# TRHPSVG_Controls_v2.net
KiCad netlist of a schematic drawn in EAGLE
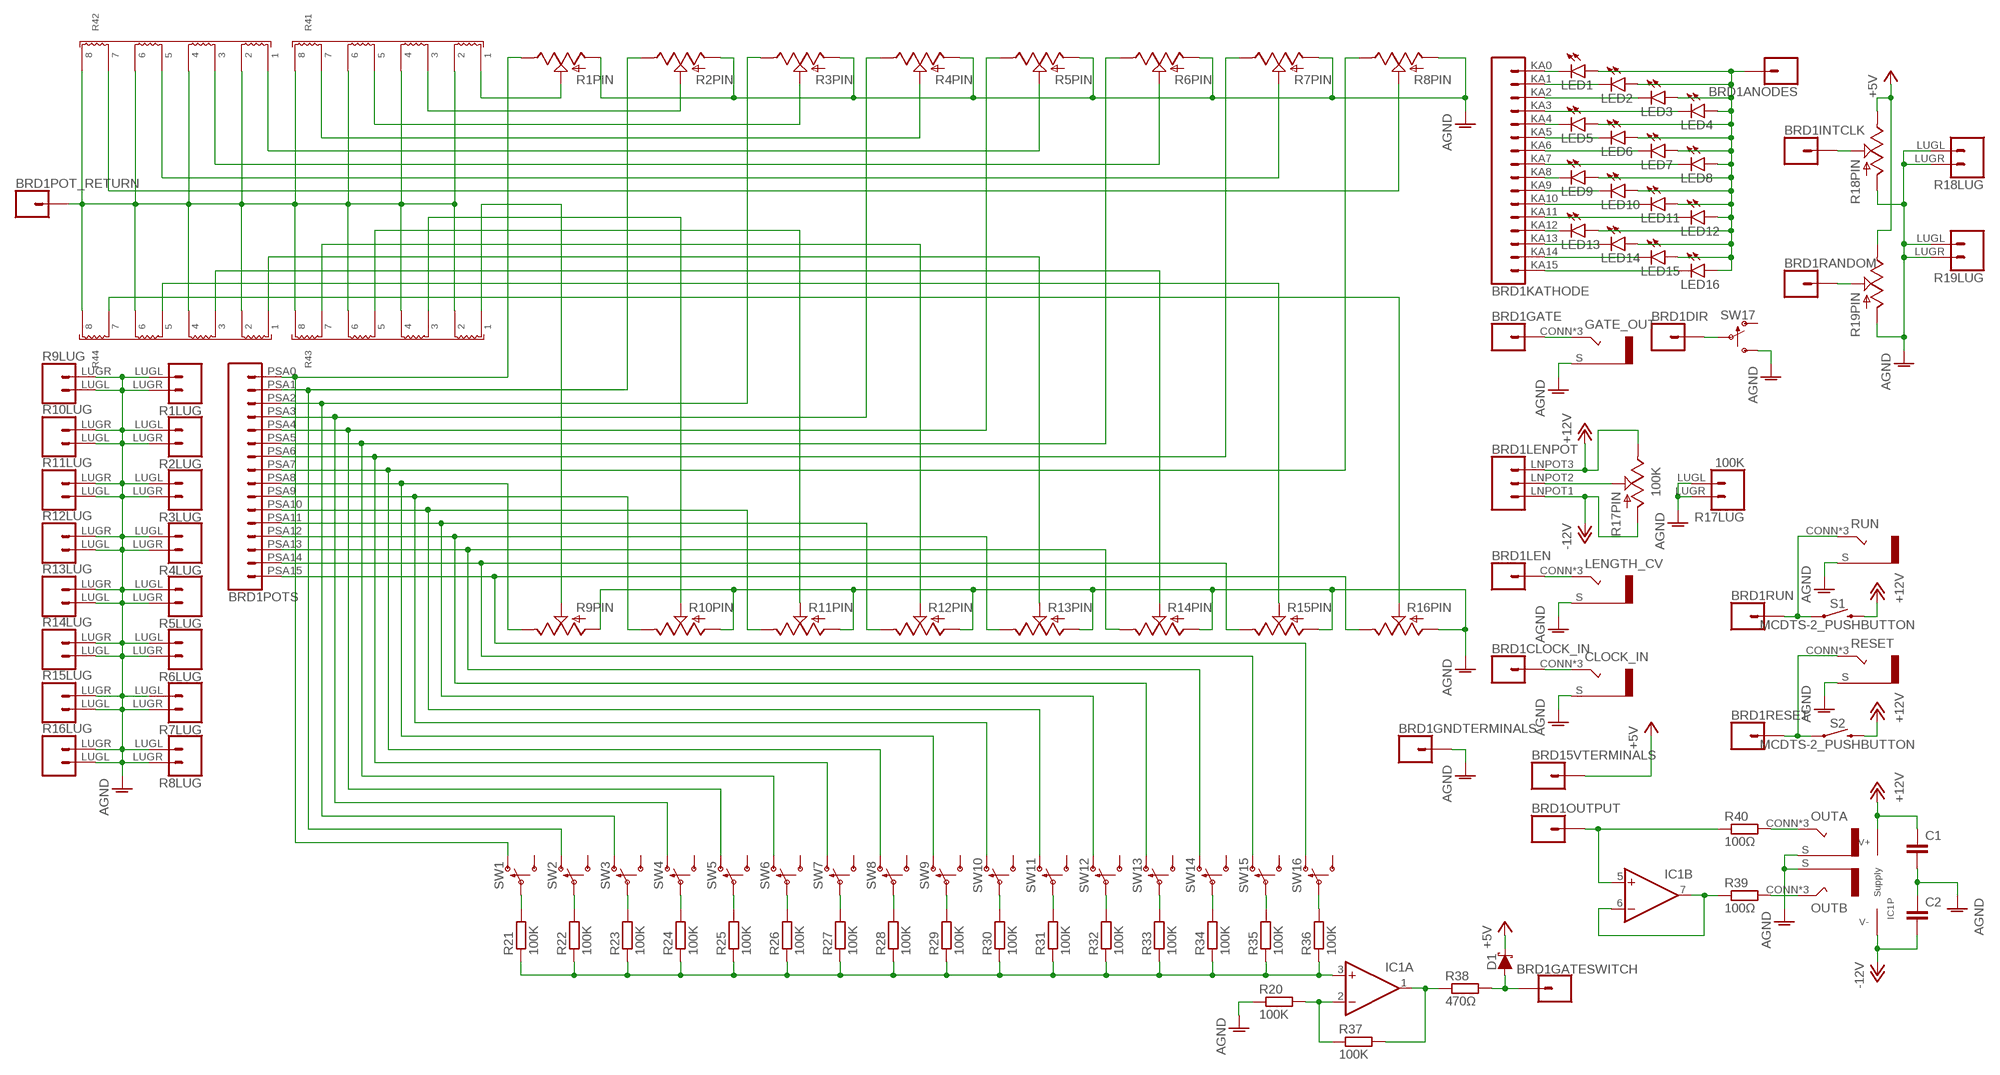
[diagram p0: schematic, sheet 1]

(export (version "E")
  (design (tool "Eeschema 10.0.6"))
  (components
    (comp (ref "BRD1")
      (value "TRHPSVG_LINK")
      (footprint "eagle-import:TRHPSVG")
      (libsource (lib "eagle-import") (part "TRHPSVG_LINK"))
    )
    (comp (ref "C1")
      (value "C-EU050-025X075")
      (footprint "eagle-import:C050-025X075")
      (libsource (lib "eagle-import") (part "C-EU050-025X075"))
    )
    (comp (ref "C2")
      (value "C-EU050-025X075")
      (footprint "eagle-import:C050-025X075")
      (libsource (lib "eagle-import") (part "C-EU050-025X075"))
    )
    (comp (ref "CLOCK_IN")
      (value "COMBI-JACK")
      (footprint "eagle-import:COMBOJACK_PANEL")
      (libsource (lib "eagle-import") (part "COMBI-JACK"))
    )
    (comp (ref "D1")
      (value "SCHOTTKY_DO35")
      (footprint "eagle-import:DO35-7")
      (libsource (lib "eagle-import") (part "SCHOTTKY_DO35"))
    )
    (comp (ref "GATE_OUT")
      (value "COMBI-JACK")
      (footprint "eagle-import:COMBOJACK_PANEL")
      (libsource (lib "eagle-import") (part "COMBI-JACK"))
    )
    (comp (ref "IC1")
      (value "TL0X2DIL")
      (footprint "eagle-import:DIL08")
      (libsource (lib "eagle-import") (part "TL0X2DIL"))
    )
    (comp (ref "LED1")
      (value "LED3MM")
      (footprint "eagle-import:LED3MM")
      (libsource (lib "eagle-import") (part "LED3MM"))
    )
    (comp (ref "LED2")
      (value "LED3MM")
      (footprint "eagle-import:LED3MM")
      (libsource (lib "eagle-import") (part "LED3MM"))
    )
    (comp (ref "LED3")
      (value "LED3MM")
      (footprint "eagle-import:LED3MM")
      (libsource (lib "eagle-import") (part "LED3MM"))
    )
    (comp (ref "LED4")
      (value "LED3MM")
      (footprint "eagle-import:LED3MM")
      (libsource (lib "eagle-import") (part "LED3MM"))
    )
    (comp (ref "LED5")
      (value "LED3MM")
      (footprint "eagle-import:LED3MM")
      (libsource (lib "eagle-import") (part "LED3MM"))
    )
    (comp (ref "LED6")
      (value "LED3MM")
      (footprint "eagle-import:LED3MM")
      (libsource (lib "eagle-import") (part "LED3MM"))
    )
    (comp (ref "LED7")
      (value "LED3MM")
      (footprint "eagle-import:LED3MM")
      (libsource (lib "eagle-import") (part "LED3MM"))
    )
    (comp (ref "LED8")
      (value "LED3MM")
      (footprint "eagle-import:LED3MM")
      (libsource (lib "eagle-import") (part "LED3MM"))
    )
    (comp (ref "LED9")
      (value "LED3MM")
      (footprint "eagle-import:LED3MM")
      (libsource (lib "eagle-import") (part "LED3MM"))
    )
    (comp (ref "LED10")
      (value "LED3MM")
      (footprint "eagle-import:LED3MM")
      (libsource (lib "eagle-import") (part "LED3MM"))
    )
    (comp (ref "LED11")
      (value "LED3MM")
      (footprint "eagle-import:LED3MM")
      (libsource (lib "eagle-import") (part "LED3MM"))
    )
    (comp (ref "LED12")
      (value "LED3MM")
      (footprint "eagle-import:LED3MM")
      (libsource (lib "eagle-import") (part "LED3MM"))
    )
    (comp (ref "LED13")
      (value "LED3MM")
      (footprint "eagle-import:LED3MM")
      (libsource (lib "eagle-import") (part "LED3MM"))
    )
    (comp (ref "LED14")
      (value "LED3MM")
      (footprint "eagle-import:LED3MM")
      (libsource (lib "eagle-import") (part "LED3MM"))
    )
    (comp (ref "LED15")
      (value "LED3MM")
      (footprint "eagle-import:LED3MM")
      (libsource (lib "eagle-import") (part "LED3MM"))
    )
    (comp (ref "LED16")
      (value "LED3MM")
      (footprint "eagle-import:LED3MM")
      (libsource (lib "eagle-import") (part "LED3MM"))
    )
    (comp (ref "LENGTH_CV")
      (value "COMBI-JACK")
      (footprint "eagle-import:COMBOJACK_PANEL")
      (libsource (lib "eagle-import") (part "COMBI-JACK"))
    )
    (comp (ref "OUTA")
      (value "COMBI-JACK")
      (footprint "eagle-import:COMBOJACK_PANEL")
      (libsource (lib "eagle-import") (part "COMBI-JACK"))
    )
    (comp (ref "OUTB")
      (value "COMBI-JACK")
      (footprint "eagle-import:COMBOJACK_PANEL")
      (libsource (lib "eagle-import") (part "COMBI-JACK"))
    )
    (comp (ref "R1")
      (value "POTENTIOMETER")
      (footprint "eagle-import:ALPHA_RV09_9MMPOT")
      (libsource (lib "eagle-import") (part "POTENTIOMETER"))
    )
    (comp (ref "R2")
      (value "POTENTIOMETER")
      (footprint "eagle-import:ALPHA_RV09_9MMPOT")
      (libsource (lib "eagle-import") (part "POTENTIOMETER"))
    )
    (comp (ref "R3")
      (value "POTENTIOMETER")
      (footprint "eagle-import:ALPHA_RV09_9MMPOT")
      (libsource (lib "eagle-import") (part "POTENTIOMETER"))
    )
    (comp (ref "R4")
      (value "POTENTIOMETER")
      (footprint "eagle-import:ALPHA_RV09_9MMPOT")
      (libsource (lib "eagle-import") (part "POTENTIOMETER"))
    )
    (comp (ref "R5")
      (value "POTENTIOMETER")
      (footprint "eagle-import:ALPHA_RV09_9MMPOT")
      (libsource (lib "eagle-import") (part "POTENTIOMETER"))
    )
    (comp (ref "R6")
      (value "POTENTIOMETER")
      (footprint "eagle-import:ALPHA_RV09_9MMPOT")
      (libsource (lib "eagle-import") (part "POTENTIOMETER"))
    )
    (comp (ref "R7")
      (value "POTENTIOMETER")
      (footprint "eagle-import:ALPHA_RV09_9MMPOT")
      (libsource (lib "eagle-import") (part "POTENTIOMETER"))
    )
    (comp (ref "R8")
      (value "POTENTIOMETER")
      (footprint "eagle-import:ALPHA_RV09_9MMPOT")
      (libsource (lib "eagle-import") (part "POTENTIOMETER"))
    )
    (comp (ref "R9")
      (value "POTENTIOMETER")
      (footprint "eagle-import:ALPHA_RV09_9MMPOT")
      (libsource (lib "eagle-import") (part "POTENTIOMETER"))
    )
    (comp (ref "R10")
      (value "POTENTIOMETER")
      (footprint "eagle-import:ALPHA_RV09_9MMPOT")
      (libsource (lib "eagle-import") (part "POTENTIOMETER"))
    )
    (comp (ref "R11")
      (value "POTENTIOMETER")
      (footprint "eagle-import:ALPHA_RV09_9MMPOT")
      (libsource (lib "eagle-import") (part "POTENTIOMETER"))
    )
    (comp (ref "R12")
      (value "POTENTIOMETER")
      (footprint "eagle-import:ALPHA_RV09_9MMPOT")
      (libsource (lib "eagle-import") (part "POTENTIOMETER"))
    )
    (comp (ref "R13")
      (value "POTENTIOMETER")
      (footprint "eagle-import:ALPHA_RV09_9MMPOT")
      (libsource (lib "eagle-import") (part "POTENTIOMETER"))
    )
    (comp (ref "R14")
      (value "POTENTIOMETER")
      (footprint "eagle-import:ALPHA_RV09_9MMPOT")
      (libsource (lib "eagle-import") (part "POTENTIOMETER"))
    )
    (comp (ref "R15")
      (value "POTENTIOMETER")
      (footprint "eagle-import:ALPHA_RV09_9MMPOT")
      (libsource (lib "eagle-import") (part "POTENTIOMETER"))
    )
    (comp (ref "R16")
      (value "POTENTIOMETER")
      (footprint "eagle-import:ALPHA_RV09_9MMPOT")
      (libsource (lib "eagle-import") (part "POTENTIOMETER"))
    )
    (comp (ref "R17")
      (value "100K")
      (footprint "eagle-import:ALPHA_RV09_9MMPOT")
      (libsource (lib "eagle-import") (part "POTENTIOMETER"))
    )
    (comp (ref "R18")
      (value "POTENTIOMETER")
      (footprint "eagle-import:ALPHA_RV09_9MMPOT")
      (libsource (lib "eagle-import") (part "POTENTIOMETER"))
    )
    (comp (ref "R19")
      (value "POTENTIOMETER")
      (footprint "eagle-import:ALPHA_RV09_9MMPOT")
      (libsource (lib "eagle-import") (part "POTENTIOMETER"))
    )
    (comp (ref "R20")
      (value "100K")
      (footprint "eagle-import:0207_10")
      (libsource (lib "eagle-import") (part "R-EU_0207/10"))
    )
    (comp (ref "R21")
      (value "100K")
      (footprint "eagle-import:0207_10")
      (libsource (lib "eagle-import") (part "R-EU_0207/10"))
    )
    (comp (ref "R22")
      (value "100K")
      (footprint "eagle-import:0207_10")
      (libsource (lib "eagle-import") (part "R-EU_0207/10"))
    )
    (comp (ref "R23")
      (value "100K")
      (footprint "eagle-import:0207_10")
      (libsource (lib "eagle-import") (part "R-EU_0207/10"))
    )
    (comp (ref "R24")
      (value "100K")
      (footprint "eagle-import:0207_10")
      (libsource (lib "eagle-import") (part "R-EU_0207/10"))
    )
    (comp (ref "R25")
      (value "100K")
      (footprint "eagle-import:0207_10")
      (libsource (lib "eagle-import") (part "R-EU_0207/10"))
    )
    (comp (ref "R26")
      (value "100K")
      (footprint "eagle-import:0207_10")
      (libsource (lib "eagle-import") (part "R-EU_0207/10"))
    )
    (comp (ref "R27")
      (value "100K")
      (footprint "eagle-import:0207_10")
      (libsource (lib "eagle-import") (part "R-EU_0207/10"))
    )
    (comp (ref "R28")
      (value "100K")
      (footprint "eagle-import:0207_10")
      (libsource (lib "eagle-import") (part "R-EU_0207/10"))
    )
    (comp (ref "R29")
      (value "100K")
      (footprint "eagle-import:0207_10")
      (libsource (lib "eagle-import") (part "R-EU_0207/10"))
    )
    (comp (ref "R30")
      (value "100K")
      (footprint "eagle-import:0207_10")
      (libsource (lib "eagle-import") (part "R-EU_0207/10"))
    )
    (comp (ref "R31")
      (value "100K")
      (footprint "eagle-import:0207_10")
      (libsource (lib "eagle-import") (part "R-EU_0207/10"))
    )
    (comp (ref "R32")
      (value "100K")
      (footprint "eagle-import:0207_10")
      (libsource (lib "eagle-import") (part "R-EU_0207/10"))
    )
    (comp (ref "R33")
      (value "100K")
      (footprint "eagle-import:0207_10")
      (libsource (lib "eagle-import") (part "R-EU_0207/10"))
    )
    (comp (ref "R34")
      (value "100K")
      (footprint "eagle-import:0207_10")
      (libsource (lib "eagle-import") (part "R-EU_0207/10"))
    )
    (comp (ref "R35")
      (value "100K")
      (footprint "eagle-import:0207_10")
      (libsource (lib "eagle-import") (part "R-EU_0207/10"))
    )
    (comp (ref "R36")
      (value "100K")
      (footprint "eagle-import:0207_10")
      (libsource (lib "eagle-import") (part "R-EU_0207/10"))
    )
    (comp (ref "R37")
      (value "100K")
      (footprint "eagle-import:0207_10")
      (libsource (lib "eagle-import") (part "R-EU_0207/10"))
    )
    (comp (ref "R38")
      (value "470Ω")
      (footprint "eagle-import:0207_10")
      (libsource (lib "eagle-import") (part "R-EU_0207/10"))
    )
    (comp (ref "R39")
      (value "100Ω")
      (footprint "eagle-import:0207_10")
      (libsource (lib "eagle-import") (part "R-EU_0207/10"))
    )
    (comp (ref "R40")
      (value "100Ω")
      (footprint "eagle-import:0207_10")
      (libsource (lib "eagle-import") (part "R-EU_0207/10"))
    )
    (comp (ref "R41")
      (value "4XISO_RESISTOR_NETWORK_2.54")
      (footprint "eagle-import:4_ISO_RES_NET_2.54")
      (libsource (lib "eagle-import") (part "4XISO_RESISTOR_NETWORK_2.54"))
    )
    (comp (ref "R42")
      (value "4XISO_RESISTOR_NETWORK_2.54")
      (footprint "eagle-import:4_ISO_RES_NET_2.54")
      (libsource (lib "eagle-import") (part "4XISO_RESISTOR_NETWORK_2.54"))
    )
    (comp (ref "R43")
      (value "4XISO_RESISTOR_NETWORK_2.54")
      (footprint "eagle-import:4_ISO_RES_NET_2.54")
      (libsource (lib "eagle-import") (part "4XISO_RESISTOR_NETWORK_2.54"))
    )
    (comp (ref "R44")
      (value "4XISO_RESISTOR_NETWORK_2.54")
      (footprint "eagle-import:4_ISO_RES_NET_2.54")
      (libsource (lib "eagle-import") (part "4XISO_RESISTOR_NETWORK_2.54"))
    )
    (comp (ref "RESET")
      (value "COMBI-JACK")
      (footprint "eagle-import:COMBOJACK_PANEL")
      (libsource (lib "eagle-import") (part "COMBI-JACK"))
    )
    (comp (ref "RUN")
      (value "COMBI-JACK")
      (footprint "eagle-import:COMBOJACK_PANEL")
      (libsource (lib "eagle-import") (part "COMBI-JACK"))
    )
    (comp (ref "S1")
      (value "MCDTS-2_PUSHBUTTON")
      (footprint "eagle-import:MCDTS-2_PUSHBUTTON")
      (libsource (lib "eagle-import") (part "MCDTS-2_PUSHBUTTON"))
    )
    (comp (ref "S2")
      (value "MCDTS-2_PUSHBUTTON")
      (footprint "eagle-import:MCDTS-2_PUSHBUTTON")
      (libsource (lib "eagle-import") (part "MCDTS-2_PUSHBUTTON"))
    )
    (comp (ref "SW1")
      (value "SPDT_SWITCHDW1")
      (footprint "eagle-import:MICRODPDT-DW1")
      (libsource (lib "eagle-import") (part "SPDT_SWITCHDW1"))
    )
    (comp (ref "SW2")
      (value "SPDT_SWITCHDW1")
      (footprint "eagle-import:MICRODPDT-DW1")
      (libsource (lib "eagle-import") (part "SPDT_SWITCHDW1"))
    )
    (comp (ref "SW3")
      (value "SPDT_SWITCHDW1")
      (footprint "eagle-import:MICRODPDT-DW1")
      (libsource (lib "eagle-import") (part "SPDT_SWITCHDW1"))
    )
    (comp (ref "SW4")
      (value "SPDT_SWITCHDW1")
      (footprint "eagle-import:MICRODPDT-DW1")
      (libsource (lib "eagle-import") (part "SPDT_SWITCHDW1"))
    )
    (comp (ref "SW5")
      (value "SPDT_SWITCHDW1")
      (footprint "eagle-import:MICRODPDT-DW1")
      (libsource (lib "eagle-import") (part "SPDT_SWITCHDW1"))
    )
    (comp (ref "SW6")
      (value "SPDT_SWITCHDW1")
      (footprint "eagle-import:MICRODPDT-DW1")
      (libsource (lib "eagle-import") (part "SPDT_SWITCHDW1"))
    )
    (comp (ref "SW7")
      (value "SPDT_SWITCHDW1")
      (footprint "eagle-import:MICRODPDT-DW1")
      (libsource (lib "eagle-import") (part "SPDT_SWITCHDW1"))
    )
    (comp (ref "SW8")
      (value "SPDT_SWITCHDW1")
      (footprint "eagle-import:MICRODPDT-DW1")
      (libsource (lib "eagle-import") (part "SPDT_SWITCHDW1"))
    )
    (comp (ref "SW9")
      (value "SPDT_SWITCHDW1")
      (footprint "eagle-import:MICRODPDT-DW1")
      (libsource (lib "eagle-import") (part "SPDT_SWITCHDW1"))
    )
    (comp (ref "SW10")
      (value "SPDT_SWITCHDW1")
      (footprint "eagle-import:MICRODPDT-DW1")
      (libsource (lib "eagle-import") (part "SPDT_SWITCHDW1"))
    )
    (comp (ref "SW11")
      (value "SPDT_SWITCHDW1")
      (footprint "eagle-import:MICRODPDT-DW1")
      (libsource (lib "eagle-import") (part "SPDT_SWITCHDW1"))
    )
    (comp (ref "SW12")
      (value "SPDT_SWITCHDW1")
      (footprint "eagle-import:MICRODPDT-DW1")
      (libsource (lib "eagle-import") (part "SPDT_SWITCHDW1"))
    )
    (comp (ref "SW13")
      (value "SPDT_SWITCHDW1")
      (footprint "eagle-import:MICRODPDT-DW1")
      (libsource (lib "eagle-import") (part "SPDT_SWITCHDW1"))
    )
    (comp (ref "SW14")
      (value "SPDT_SWITCHDW1")
      (footprint "eagle-import:MICRODPDT-DW1")
      (libsource (lib "eagle-import") (part "SPDT_SWITCHDW1"))
    )
    (comp (ref "SW15")
      (value "SPDT_SWITCHDW1")
      (footprint "eagle-import:MICRODPDT-DW1")
      (libsource (lib "eagle-import") (part "SPDT_SWITCHDW1"))
    )
    (comp (ref "SW16")
      (value "SPDT_SWITCHDW1")
      (footprint "eagle-import:MICRODPDT-DW1")
      (libsource (lib "eagle-import") (part "SPDT_SWITCHDW1"))
    )
    (comp (ref "SW17")
      (value "SPDT_SWITCHDW1")
      (footprint "eagle-import:MICRODPDT-DW1")
      (libsource (lib "eagle-import") (part "SPDT_SWITCHDW1"))
    )
  )
  (nets
    (net (code "1") (name "+5V") (class "Default")
      (node (ref "BRD1") (pin "5V1") (pinfunction "1_5V1") (pintype "passive"))
      (node (ref "BRD1") (pin "5V2") (pinfunction "1_5V2") (pintype "passive"))
      (node (ref "BRD1") (pin "5V3") (pinfunction "1_5V3") (pintype "passive"))
      (node (ref "D1") (pin "C") (pinfunction "C_C") (pintype "passive"))
      (node (ref "R18") (pin "C3") (pinfunction "B_C3") (pintype "passive"))
      (node (ref "R19") (pin "C3") (pinfunction "B_C3") (pintype "passive"))
    )
    (net (code "2") (name "+12V") (class "Default")
      (node (ref "BRD1") (pin "LNPOT3") (pinfunction "3_LNPOT3") (pintype "passive"))
      (node (ref "C1") (pin "1") (pinfunction "1_1") (pintype "passive"))
      (node (ref "IC1") (pin "8") (pinfunction "V+_8") (pintype "bidirectional"))
      (node (ref "R17") (pin "C3") (pinfunction "B_C3") (pintype "passive"))
      (node (ref "S1") (pin "P$3") (pinfunction "2_P$3") (pintype "passive"))
      (node (ref "S1") (pin "P$4") (pinfunction "2_P$4") (pintype "passive"))
      (node (ref "S2") (pin "P$3") (pinfunction "2_P$3") (pintype "passive"))
      (node (ref "S2") (pin "P$4") (pinfunction "2_P$4") (pintype "passive"))
    )
    (net (code "3") (name "-12V") (class "Default")
      (node (ref "BRD1") (pin "LNPOT1") (pinfunction "1_LNPOT1") (pintype "passive"))
      (node (ref "C2") (pin "2") (pinfunction "2_2") (pintype "passive"))
      (node (ref "IC1") (pin "4") (pinfunction "V-_4") (pintype "bidirectional"))
      (node (ref "R17") (pin "C1") (pinfunction "A_C1") (pintype "passive"))
    )
    (net (code "4") (name "AGND") (class "Default")
      (node (ref "BRD1") (pin "GND1") (pinfunction "1_GND1") (pintype "passive"))
      (node (ref "BRD1") (pin "GND2") (pinfunction "1_GND2") (pintype "passive"))
      (node (ref "BRD1") (pin "GND3") (pinfunction "1_GND3") (pintype "passive"))
      (node (ref "C1") (pin "2") (pinfunction "2_2") (pintype "passive"))
      (node (ref "C2") (pin "1") (pinfunction "1_1") (pintype "passive"))
      (node (ref "CLOCK_IN") (pin "S") (pinfunction "S_S") (pintype "passive"))
      (node (ref "GATE_OUT") (pin "S") (pinfunction "S_S") (pintype "passive"))
      (node (ref "LENGTH_CV") (pin "S") (pinfunction "S_S") (pintype "passive"))
      (node (ref "OUTA") (pin "S") (pinfunction "S_S") (pintype "passive"))
      (node (ref "OUTB") (pin "S") (pinfunction "S_S") (pintype "passive"))
      (node (ref "R1") (pin "C1") (pinfunction "A_C1") (pintype "passive"))
      (node (ref "R1") (pin "LUGL") (pinfunction "1_LUGL") (pintype "passive"))
      (node (ref "R1") (pin "LUGR") (pinfunction "2_LUGR") (pintype "passive"))
      (node (ref "R10") (pin "C1") (pinfunction "A_C1") (pintype "passive"))
      (node (ref "R10") (pin "LUGL") (pinfunction "1_LUGL") (pintype "passive"))
      (node (ref "R10") (pin "LUGR") (pinfunction "2_LUGR") (pintype "passive"))
      (node (ref "R11") (pin "C1") (pinfunction "A_C1") (pintype "passive"))
      (node (ref "R11") (pin "LUGL") (pinfunction "1_LUGL") (pintype "passive"))
      (node (ref "R11") (pin "LUGR") (pinfunction "2_LUGR") (pintype "passive"))
      (node (ref "R12") (pin "C1") (pinfunction "A_C1") (pintype "passive"))
      (node (ref "R12") (pin "LUGL") (pinfunction "1_LUGL") (pintype "passive"))
      (node (ref "R12") (pin "LUGR") (pinfunction "2_LUGR") (pintype "passive"))
      (node (ref "R13") (pin "C1") (pinfunction "A_C1") (pintype "passive"))
      (node (ref "R13") (pin "LUGL") (pinfunction "1_LUGL") (pintype "passive"))
      (node (ref "R13") (pin "LUGR") (pinfunction "2_LUGR") (pintype "passive"))
      (node (ref "R14") (pin "C1") (pinfunction "A_C1") (pintype "passive"))
      (node (ref "R14") (pin "LUGL") (pinfunction "1_LUGL") (pintype "passive"))
      (node (ref "R14") (pin "LUGR") (pinfunction "2_LUGR") (pintype "passive"))
      (node (ref "R15") (pin "C1") (pinfunction "A_C1") (pintype "passive"))
      (node (ref "R15") (pin "LUGL") (pinfunction "1_LUGL") (pintype "passive"))
      (node (ref "R15") (pin "LUGR") (pinfunction "2_LUGR") (pintype "passive"))
      (node (ref "R16") (pin "C1") (pinfunction "A_C1") (pintype "passive"))
      (node (ref "R16") (pin "LUGL") (pinfunction "1_LUGL") (pintype "passive"))
      (node (ref "R16") (pin "LUGR") (pinfunction "2_LUGR") (pintype "passive"))
      (node (ref "R17") (pin "LUGL") (pinfunction "1_LUGL") (pintype "passive"))
      (node (ref "R17") (pin "LUGR") (pinfunction "2_LUGR") (pintype "passive"))
      (node (ref "R18") (pin "C1") (pinfunction "A_C1") (pintype "passive"))
      (node (ref "R18") (pin "LUGL") (pinfunction "1_LUGL") (pintype "passive"))
      (node (ref "R18") (pin "LUGR") (pinfunction "2_LUGR") (pintype "passive"))
      (node (ref "R19") (pin "C1") (pinfunction "A_C1") (pintype "passive"))
      (node (ref "R19") (pin "LUGL") (pinfunction "1_LUGL") (pintype "passive"))
      (node (ref "R19") (pin "LUGR") (pinfunction "2_LUGR") (pintype "passive"))
      (node (ref "R2") (pin "C1") (pinfunction "A_C1") (pintype "passive"))
      (node (ref "R2") (pin "LUGL") (pinfunction "1_LUGL") (pintype "passive"))
      (node (ref "R2") (pin "LUGR") (pinfunction "2_LUGR") (pintype "passive"))
      (node (ref "R20") (pin "1") (pinfunction "1_1") (pintype "passive"))
      (node (ref "R3") (pin "C1") (pinfunction "A_C1") (pintype "passive"))
      (node (ref "R3") (pin "LUGL") (pinfunction "1_LUGL") (pintype "passive"))
      (node (ref "R3") (pin "LUGR") (pinfunction "2_LUGR") (pintype "passive"))
      (node (ref "R4") (pin "C1") (pinfunction "A_C1") (pintype "passive"))
      (node (ref "R4") (pin "LUGL") (pinfunction "1_LUGL") (pintype "passive"))
      (node (ref "R4") (pin "LUGR") (pinfunction "2_LUGR") (pintype "passive"))
      (node (ref "R5") (pin "C1") (pinfunction "A_C1") (pintype "passive"))
      (node (ref "R5") (pin "LUGL") (pinfunction "1_LUGL") (pintype "passive"))
      (node (ref "R5") (pin "LUGR") (pinfunction "2_LUGR") (pintype "passive"))
      (node (ref "R6") (pin "C1") (pinfunction "A_C1") (pintype "passive"))
      (node (ref "R6") (pin "LUGL") (pinfunction "1_LUGL") (pintype "passive"))
      (node (ref "R6") (pin "LUGR") (pinfunction "2_LUGR") (pintype "passive"))
      (node (ref "R7") (pin "C1") (pinfunction "A_C1") (pintype "passive"))
      (node (ref "R7") (pin "LUGL") (pinfunction "1_LUGL") (pintype "passive"))
      (node (ref "R7") (pin "LUGR") (pinfunction "2_LUGR") (pintype "passive"))
      (node (ref "R8") (pin "C1") (pinfunction "A_C1") (pintype "passive"))
      (node (ref "R8") (pin "LUGL") (pinfunction "1_LUGL") (pintype "passive"))
      (node (ref "R8") (pin "LUGR") (pinfunction "2_LUGR") (pintype "passive"))
      (node (ref "R9") (pin "C1") (pinfunction "A_C1") (pintype "passive"))
      (node (ref "R9") (pin "LUGL") (pinfunction "1_LUGL") (pintype "passive"))
      (node (ref "R9") (pin "LUGR") (pinfunction "2_LUGR") (pintype "passive"))
      (node (ref "RESET") (pin "S") (pinfunction "S_S") (pintype "passive"))
      (node (ref "RUN") (pin "S") (pinfunction "S_S") (pintype "passive"))
      (node (ref "SW17") (pin "C3") (pinfunction "S_C3") (pintype "passive"))
    )
    (net (code "5") (name "Net-(BRD1B-1-PadAN1)") (class "Default")
      (node (ref "BRD1") (pin "AN1") (pinfunction "1_AN1") (pintype "passive"))
      (node (ref "BRD1") (pin "AN2") (pinfunction "1_AN2") (pintype "passive"))
      (node (ref "LED1") (pin "A") (pinfunction "A_A") (pintype "passive"))
      (node (ref "LED10") (pin "A") (pinfunction "A_A") (pintype "passive"))
      (node (ref "LED11") (pin "A") (pinfunction "A_A") (pintype "passive"))
      (node (ref "LED12") (pin "A") (pinfunction "A_A") (pintype "passive"))
      (node (ref "LED13") (pin "A") (pinfunction "A_A") (pintype "passive"))
      (node (ref "LED14") (pin "A") (pinfunction "A_A") (pintype "passive"))
      (node (ref "LED15") (pin "A") (pinfunction "A_A") (pintype "passive"))
      (node (ref "LED16") (pin "A") (pinfunction "A_A") (pintype "passive"))
      (node (ref "LED2") (pin "A") (pinfunction "A_A") (pintype "passive"))
      (node (ref "LED3") (pin "A") (pinfunction "A_A") (pintype "passive"))
      (node (ref "LED4") (pin "A") (pinfunction "A_A") (pintype "passive"))
      (node (ref "LED5") (pin "A") (pinfunction "A_A") (pintype "passive"))
      (node (ref "LED6") (pin "A") (pinfunction "A_A") (pintype "passive"))
      (node (ref "LED7") (pin "A") (pinfunction "A_A") (pintype "passive"))
      (node (ref "LED8") (pin "A") (pinfunction "A_A") (pintype "passive"))
      (node (ref "LED9") (pin "A") (pinfunction "A_A") (pintype "passive"))
    )
    (net (code "6") (name "Net-(BRD1C-1)") (class "Default")
      (node (ref "BRD1") (pin "CLKIN") (pinfunction "1_CLKIN") (pintype "passive"))
      (node (ref "CLOCK_IN") (pin "CONN") (pinfunction "T_CONN") (pintype "passive"))
      (node (ref "CLOCK_IN") (pin "T1") (pinfunction "T_T1") (pintype "passive"))
      (node (ref "CLOCK_IN") (pin "T2") (pinfunction "T_T2") (pintype "passive"))
    )
    (net (code "7") (name "Net-(BRD1D-1)") (class "Default")
      (node (ref "BRD1") (pin "DIR") (pinfunction "1_DIR") (pintype "passive"))
      (node (ref "SW17") (pin "C2") (pinfunction "P_C2") (pintype "passive"))
    )
    (net (code "8") (name "Net-(BRD1E-1)") (class "Default")
      (node (ref "BRD1") (pin "GATE") (pinfunction "1_GATE") (pintype "passive"))
      (node (ref "GATE_OUT") (pin "CONN") (pinfunction "T_CONN") (pintype "passive"))
      (node (ref "GATE_OUT") (pin "T1") (pinfunction "T_T1") (pintype "passive"))
      (node (ref "GATE_OUT") (pin "T2") (pinfunction "T_T2") (pintype "passive"))
    )
    (net (code "9") (name "Net-(BRD1F-1)") (class "Default")
      (node (ref "BRD1") (pin "GSW") (pinfunction "1_GSW") (pintype "passive"))
      (node (ref "D1") (pin "A") (pinfunction "A_A") (pintype "passive"))
      (node (ref "R38") (pin "2") (pinfunction "2_2") (pintype "passive"))
    )
    (net (code "10") (name "Net-(BRD1H-1)") (class "Default")
      (node (ref "BRD1") (pin "INTC") (pinfunction "1_INTC") (pintype "passive"))
      (node (ref "R18") (pin "C2") (pinfunction "W_C2") (pintype "passive"))
    )
    (net (code "11") (name "Net-(BRD1I-1)") (class "Default")
      (node (ref "BRD1") (pin "KA0") (pinfunction "1_KA0") (pintype "passive"))
      (node (ref "LED1") (pin "K") (pinfunction "C_K") (pintype "passive"))
    )
    (net (code "12") (name "Net-(BRD1I-2)") (class "Default")
      (node (ref "BRD1") (pin "KA1") (pinfunction "2_KA1") (pintype "passive"))
      (node (ref "LED2") (pin "K") (pinfunction "C_K") (pintype "passive"))
    )
    (net (code "13") (name "Net-(BRD1I-3)") (class "Default")
      (node (ref "BRD1") (pin "KA2") (pinfunction "3_KA2") (pintype "passive"))
      (node (ref "LED3") (pin "K") (pinfunction "C_K") (pintype "passive"))
    )
    (net (code "14") (name "Net-(BRD1I-4)") (class "Default")
      (node (ref "BRD1") (pin "KA3") (pinfunction "4_KA3") (pintype "passive"))
      (node (ref "LED4") (pin "K") (pinfunction "C_K") (pintype "passive"))
    )
    (net (code "15") (name "Net-(BRD1I-5)") (class "Default")
      (node (ref "BRD1") (pin "KA4") (pinfunction "5_KA4") (pintype "passive"))
      (node (ref "LED5") (pin "K") (pinfunction "C_K") (pintype "passive"))
    )
    (net (code "16") (name "Net-(BRD1I-6)") (class "Default")
      (node (ref "BRD1") (pin "KA5") (pinfunction "6_KA5") (pintype "passive"))
      (node (ref "LED6") (pin "K") (pinfunction "C_K") (pintype "passive"))
    )
    (net (code "17") (name "Net-(BRD1I-7)") (class "Default")
      (node (ref "BRD1") (pin "KA6") (pinfunction "7_KA6") (pintype "passive"))
      (node (ref "LED7") (pin "K") (pinfunction "C_K") (pintype "passive"))
    )
    (net (code "18") (name "Net-(BRD1I-8)") (class "Default")
      (node (ref "BRD1") (pin "KA7") (pinfunction "8_KA7") (pintype "passive"))
      (node (ref "LED8") (pin "K") (pinfunction "C_K") (pintype "passive"))
    )
    (net (code "19") (name "Net-(BRD1I-9)") (class "Default")
      (node (ref "BRD1") (pin "KA8") (pinfunction "9_KA8") (pintype "passive"))
      (node (ref "LED9") (pin "K") (pinfunction "C_K") (pintype "passive"))
    )
    (net (code "20") (name "Net-(BRD1I-10)") (class "Default")
      (node (ref "BRD1") (pin "KA9") (pinfunction "10_KA9") (pintype "passive"))
      (node (ref "LED10") (pin "K") (pinfunction "C_K") (pintype "passive"))
    )
    (net (code "21") (name "Net-(BRD1I-11)") (class "Default")
      (node (ref "BRD1") (pin "KA10") (pinfunction "11_KA10") (pintype "passive"))
      (node (ref "LED11") (pin "K") (pinfunction "C_K") (pintype "passive"))
    )
    (net (code "22") (name "Net-(BRD1I-12)") (class "Default")
      (node (ref "BRD1") (pin "KA11") (pinfunction "12_KA11") (pintype "passive"))
      (node (ref "LED12") (pin "K") (pinfunction "C_K") (pintype "passive"))
    )
    (net (code "23") (name "Net-(BRD1I-13)") (class "Default")
      (node (ref "BRD1") (pin "KA12") (pinfunction "13_KA12") (pintype "passive"))
      (node (ref "LED13") (pin "K") (pinfunction "C_K") (pintype "passive"))
    )
    (net (code "24") (name "Net-(BRD1I-14)") (class "Default")
      (node (ref "BRD1") (pin "KA13") (pinfunction "14_KA13") (pintype "passive"))
      (node (ref "LED14") (pin "K") (pinfunction "C_K") (pintype "passive"))
    )
    (net (code "25") (name "Net-(BRD1I-15)") (class "Default")
      (node (ref "BRD1") (pin "KA14") (pinfunction "15_KA14") (pintype "passive"))
      (node (ref "LED15") (pin "K") (pinfunction "C_K") (pintype "passive"))
    )
    (net (code "26") (name "Net-(BRD1I-16)") (class "Default")
      (node (ref "BRD1") (pin "KA15") (pinfunction "16_KA15") (pintype "passive"))
      (node (ref "LED16") (pin "K") (pinfunction "C_K") (pintype "passive"))
    )
    (net (code "27") (name "Net-(BRD1J-1)") (class "Default")
      (node (ref "BRD1") (pin "LENGTH") (pinfunction "1_LENGTH") (pintype "passive"))
      (node (ref "LENGTH_CV") (pin "CONN") (pinfunction "T_CONN") (pintype "passive"))
      (node (ref "LENGTH_CV") (pin "T1") (pinfunction "T_T1") (pintype "passive"))
      (node (ref "LENGTH_CV") (pin "T2") (pinfunction "T_T2") (pintype "passive"))
    )
    (net (code "28") (name "Net-(BRD1K-2)") (class "Default")
      (node (ref "BRD1") (pin "LNPOT2") (pinfunction "2_LNPOT2") (pintype "passive"))
      (node (ref "R17") (pin "C2") (pinfunction "W_C2") (pintype "passive"))
    )
    (net (code "29") (name "Net-(BRD1L-1)") (class "Default")
      (node (ref "BRD1") (pin "SEQ") (pinfunction "1_SEQ") (pintype "passive"))
      (node (ref "IC1") (pin "5") (pinfunction "+IN_5") (pintype "input"))
      (node (ref "R40") (pin "1") (pinfunction "1_1") (pintype "passive"))
    )
    (net (code "30") (name "Net-(BRD1M-1)") (class "Default")
      (node (ref "BRD1") (pin "PSA0") (pinfunction "1_PSA0") (pintype "passive"))
      (node (ref "R1") (pin "C3") (pinfunction "B_C3") (pintype "passive"))
      (node (ref "SW1") (pin "C1") (pinfunction "O_C1") (pintype "passive"))
    )
    (net (code "31") (name "Net-(BRD1M-2)") (class "Default")
      (node (ref "BRD1") (pin "PSA1") (pinfunction "2_PSA1") (pintype "passive"))
      (node (ref "R2") (pin "C3") (pinfunction "B_C3") (pintype "passive"))
      (node (ref "SW2") (pin "C1") (pinfunction "O_C1") (pintype "passive"))
    )
    (net (code "32") (name "Net-(BRD1M-3)") (class "Default")
      (node (ref "BRD1") (pin "PSA2") (pinfunction "3_PSA2") (pintype "passive"))
      (node (ref "R3") (pin "C3") (pinfunction "B_C3") (pintype "passive"))
      (node (ref "SW3") (pin "C1") (pinfunction "O_C1") (pintype "passive"))
    )
    (net (code "33") (name "Net-(BRD1M-4)") (class "Default")
      (node (ref "BRD1") (pin "PSA3") (pinfunction "4_PSA3") (pintype "passive"))
      (node (ref "R4") (pin "C3") (pinfunction "B_C3") (pintype "passive"))
      (node (ref "SW4") (pin "C1") (pinfunction "O_C1") (pintype "passive"))
    )
    (net (code "34") (name "Net-(BRD1M-5)") (class "Default")
      (node (ref "BRD1") (pin "PSA4") (pinfunction "5_PSA4") (pintype "passive"))
      (node (ref "R5") (pin "C3") (pinfunction "B_C3") (pintype "passive"))
      (node (ref "SW5") (pin "C1") (pinfunction "O_C1") (pintype "passive"))
    )
    (net (code "35") (name "Net-(BRD1M-6)") (class "Default")
      (node (ref "BRD1") (pin "PSA5") (pinfunction "6_PSA5") (pintype "passive"))
      (node (ref "R6") (pin "C3") (pinfunction "B_C3") (pintype "passive"))
      (node (ref "SW6") (pin "C1") (pinfunction "O_C1") (pintype "passive"))
    )
    (net (code "36") (name "Net-(BRD1M-7)") (class "Default")
      (node (ref "BRD1") (pin "PSA6") (pinfunction "7_PSA6") (pintype "passive"))
      (node (ref "R7") (pin "C3") (pinfunction "B_C3") (pintype "passive"))
      (node (ref "SW7") (pin "C1") (pinfunction "O_C1") (pintype "passive"))
    )
    (net (code "37") (name "Net-(BRD1M-8)") (class "Default")
      (node (ref "BRD1") (pin "PSA7") (pinfunction "8_PSA7") (pintype "passive"))
      (node (ref "R8") (pin "C3") (pinfunction "B_C3") (pintype "passive"))
      (node (ref "SW8") (pin "C1") (pinfunction "O_C1") (pintype "passive"))
    )
    (net (code "38") (name "Net-(BRD1M-9)") (class "Default")
      (node (ref "BRD1") (pin "PSA8") (pinfunction "9_PSA8") (pintype "passive"))
      (node (ref "R9") (pin "C3") (pinfunction "B_C3") (pintype "passive"))
      (node (ref "SW9") (pin "C1") (pinfunction "O_C1") (pintype "passive"))
    )
    (net (code "39") (name "Net-(BRD1M-10)") (class "Default")
      (node (ref "BRD1") (pin "PSA9") (pinfunction "10_PSA9") (pintype "passive"))
      (node (ref "R10") (pin "C3") (pinfunction "B_C3") (pintype "passive"))
      (node (ref "SW10") (pin "C1") (pinfunction "O_C1") (pintype "passive"))
    )
    (net (code "40") (name "Net-(BRD1M-11)") (class "Default")
      (node (ref "BRD1") (pin "PSA10") (pinfunction "11_PSA10") (pintype "passive"))
      (node (ref "R11") (pin "C3") (pinfunction "B_C3") (pintype "passive"))
      (node (ref "SW11") (pin "C1") (pinfunction "O_C1") (pintype "passive"))
    )
    (net (code "41") (name "Net-(BRD1M-12)") (class "Default")
      (node (ref "BRD1") (pin "PSA11") (pinfunction "12_PSA11") (pintype "passive"))
      (node (ref "R12") (pin "C3") (pinfunction "B_C3") (pintype "passive"))
      (node (ref "SW12") (pin "C1") (pinfunction "O_C1") (pintype "passive"))
    )
    (net (code "42") (name "Net-(BRD1M-13)") (class "Default")
      (node (ref "BRD1") (pin "PSA12") (pinfunction "13_PSA12") (pintype "passive"))
      (node (ref "R13") (pin "C3") (pinfunction "B_C3") (pintype "passive"))
      (node (ref "SW13") (pin "C1") (pinfunction "O_C1") (pintype "passive"))
    )
    (net (code "43") (name "Net-(BRD1M-14)") (class "Default")
      (node (ref "BRD1") (pin "PSA13") (pinfunction "14_PSA13") (pintype "passive"))
      (node (ref "R14") (pin "C3") (pinfunction "B_C3") (pintype "passive"))
      (node (ref "SW14") (pin "C1") (pinfunction "O_C1") (pintype "passive"))
    )
    (net (code "44") (name "Net-(BRD1M-15)") (class "Default")
      (node (ref "BRD1") (pin "PSA14") (pinfunction "15_PSA14") (pintype "passive"))
      (node (ref "R15") (pin "C3") (pinfunction "B_C3") (pintype "passive"))
      (node (ref "SW15") (pin "C1") (pinfunction "O_C1") (pintype "passive"))
    )
    (net (code "45") (name "Net-(BRD1M-16)") (class "Default")
      (node (ref "BRD1") (pin "PSA15") (pinfunction "16_PSA15") (pintype "passive"))
      (node (ref "R16") (pin "C3") (pinfunction "B_C3") (pintype "passive"))
      (node (ref "SW16") (pin "C1") (pinfunction "O_C1") (pintype "passive"))
    )
    (net (code "46") (name "Net-(BRD1N-1)") (class "Default")
      (node (ref "BRD1") (pin "POT-R") (pinfunction "1_POT-R") (pintype "passive"))
      (node (ref "R41") (pin "P$2") (pinfunction "P$2_P$2") (pintype "bidirectional"))
      (node (ref "R41") (pin "P$4") (pinfunction "P$4_P$4") (pintype "bidirectional"))
      (node (ref "R41") (pin "P$6") (pinfunction "P$6_P$6") (pintype "bidirectional"))
      (node (ref "R41") (pin "P$8") (pinfunction "P$8_P$8") (pintype "bidirectional"))
      (node (ref "R42") (pin "P$2") (pinfunction "P$2_P$2") (pintype "bidirectional"))
      (node (ref "R42") (pin "P$4") (pinfunction "P$4_P$4") (pintype "bidirectional"))
      (node (ref "R42") (pin "P$6") (pinfunction "P$6_P$6") (pintype "bidirectional"))
      (node (ref "R42") (pin "P$8") (pinfunction "P$8_P$8") (pintype "bidirectional"))
      (node (ref "R43") (pin "P$2") (pinfunction "P$2_P$2") (pintype "bidirectional"))
      (node (ref "R43") (pin "P$4") (pinfunction "P$4_P$4") (pintype "bidirectional"))
      (node (ref "R43") (pin "P$6") (pinfunction "P$6_P$6") (pintype "bidirectional"))
      (node (ref "R43") (pin "P$8") (pinfunction "P$8_P$8") (pintype "bidirectional"))
      (node (ref "R44") (pin "P$2") (pinfunction "P$2_P$2") (pintype "bidirectional"))
      (node (ref "R44") (pin "P$4") (pinfunction "P$4_P$4") (pintype "bidirectional"))
      (node (ref "R44") (pin "P$6") (pinfunction "P$6_P$6") (pintype "bidirectional"))
      (node (ref "R44") (pin "P$8") (pinfunction "P$8_P$8") (pintype "bidirectional"))
    )
    (net (code "47") (name "Net-(BRD1O-1)") (class "Default")
      (node (ref "BRD1") (pin "RND") (pinfunction "1_RND") (pintype "passive"))
      (node (ref "R19") (pin "C2") (pinfunction "W_C2") (pintype "passive"))
    )
    (net (code "48") (name "Net-(BRD1P-1)") (class "Default")
      (node (ref "BRD1") (pin "SRST") (pinfunction "1_SRST") (pintype "passive"))
      (node (ref "RESET") (pin "CONN") (pinfunction "T_CONN") (pintype "passive"))
      (node (ref "RESET") (pin "T1") (pinfunction "T_T1") (pintype "passive"))
      (node (ref "RESET") (pin "T2") (pinfunction "T_T2") (pintype "passive"))
      (node (ref "S2") (pin "P$1") (pinfunction "1_P$1") (pintype "passive"))
      (node (ref "S2") (pin "P$2") (pinfunction "1_P$2") (pintype "passive"))
    )
    (net (code "49") (name "Net-(BRD1Q-1)") (class "Default")
      (node (ref "BRD1") (pin "RUN") (pinfunction "1_RUN") (pintype "passive"))
      (node (ref "RUN") (pin "CONN") (pinfunction "T_CONN") (pintype "passive"))
      (node (ref "RUN") (pin "T1") (pinfunction "T_T1") (pintype "passive"))
      (node (ref "RUN") (pin "T2") (pinfunction "T_T2") (pintype "passive"))
      (node (ref "S1") (pin "P$1") (pinfunction "1_P$1") (pintype "passive"))
      (node (ref "S1") (pin "P$2") (pinfunction "1_P$2") (pintype "passive"))
    )
    (net (code "50") (name "Net-(IC1A-+IN)") (class "Default")
      (node (ref "IC1") (pin "3") (pinfunction "+IN_3") (pintype "input"))
      (node (ref "R21") (pin "1") (pinfunction "1_1") (pintype "passive"))
      (node (ref "R22") (pin "1") (pinfunction "1_1") (pintype "passive"))
      (node (ref "R23") (pin "1") (pinfunction "1_1") (pintype "passive"))
      (node (ref "R24") (pin "1") (pinfunction "1_1") (pintype "passive"))
      (node (ref "R25") (pin "1") (pinfunction "1_1") (pintype "passive"))
      (node (ref "R26") (pin "1") (pinfunction "1_1") (pintype "passive"))
      (node (ref "R27") (pin "1") (pinfunction "1_1") (pintype "passive"))
      (node (ref "R28") (pin "1") (pinfunction "1_1") (pintype "passive"))
      (node (ref "R29") (pin "1") (pinfunction "1_1") (pintype "passive"))
      (node (ref "R30") (pin "1") (pinfunction "1_1") (pintype "passive"))
      (node (ref "R31") (pin "1") (pinfunction "1_1") (pintype "passive"))
      (node (ref "R32") (pin "1") (pinfunction "1_1") (pintype "passive"))
      (node (ref "R33") (pin "1") (pinfunction "1_1") (pintype "passive"))
      (node (ref "R34") (pin "1") (pinfunction "1_1") (pintype "passive"))
      (node (ref "R35") (pin "1") (pinfunction "1_1") (pintype "passive"))
      (node (ref "R36") (pin "1") (pinfunction "1_1") (pintype "passive"))
    )
    (net (code "51") (name "Net-(IC1A--IN)") (class "Default")
      (node (ref "IC1") (pin "2") (pinfunction "-IN_2") (pintype "input"))
      (node (ref "R20") (pin "2") (pinfunction "2_2") (pintype "passive"))
      (node (ref "R37") (pin "1") (pinfunction "1_1") (pintype "passive"))
    )
    (net (code "52") (name "Net-(IC1A-OUT)") (class "Default")
      (node (ref "IC1") (pin "1") (pinfunction "OUT_1") (pintype "output"))
      (node (ref "R37") (pin "2") (pinfunction "2_2") (pintype "passive"))
      (node (ref "R38") (pin "1") (pinfunction "1_1") (pintype "passive"))
    )
    (net (code "53") (name "Net-(IC1B--IN)") (class "Default")
      (node (ref "IC1") (pin "6") (pinfunction "-IN_6") (pintype "input"))
      (node (ref "IC1") (pin "7") (pinfunction "OUT_7") (pintype "output"))
      (node (ref "R39") (pin "1") (pinfunction "1_1") (pintype "passive"))
    )
    (net (code "54") (name "Net-(OUTA-T-PadCONN)") (class "Default")
      (node (ref "OUTA") (pin "CONN") (pinfunction "T_CONN") (pintype "passive"))
      (node (ref "OUTA") (pin "T1") (pinfunction "T_T1") (pintype "passive"))
      (node (ref "OUTA") (pin "T2") (pinfunction "T_T2") (pintype "passive"))
      (node (ref "R40") (pin "2") (pinfunction "2_2") (pintype "passive"))
    )
    (net (code "55") (name "Net-(OUTB-T-PadCONN)") (class "Default")
      (node (ref "OUTB") (pin "CONN") (pinfunction "T_CONN") (pintype "passive"))
      (node (ref "OUTB") (pin "T1") (pinfunction "T_T1") (pintype "passive"))
      (node (ref "OUTB") (pin "T2") (pinfunction "T_T2") (pintype "passive"))
      (node (ref "R39") (pin "2") (pinfunction "2_2") (pintype "passive"))
    )
    (net (code "56") (name "Net-(R1B-W)") (class "Default")
      (node (ref "R1") (pin "C2") (pinfunction "W_C2") (pintype "passive"))
      (node (ref "R41") (pin "P$1") (pinfunction "P$1_P$1") (pintype "bidirectional"))
    )
    (net (code "57") (name "Net-(R2B-W)") (class "Default")
      (node (ref "R2") (pin "C2") (pinfunction "W_C2") (pintype "passive"))
      (node (ref "R41") (pin "P$3") (pinfunction "P$3_P$3") (pintype "bidirectional"))
    )
    (net (code "58") (name "Net-(R3B-W)") (class "Default")
      (node (ref "R3") (pin "C2") (pinfunction "W_C2") (pintype "passive"))
      (node (ref "R41") (pin "P$5") (pinfunction "P$5_P$5") (pintype "bidirectional"))
    )
    (net (code "59") (name "Net-(R4B-W)") (class "Default")
      (node (ref "R4") (pin "C2") (pinfunction "W_C2") (pintype "passive"))
      (node (ref "R41") (pin "P$7") (pinfunction "P$7_P$7") (pintype "bidirectional"))
    )
    (net (code "60") (name "Net-(R5B-W)") (class "Default")
      (node (ref "R42") (pin "P$1") (pinfunction "P$1_P$1") (pintype "bidirectional"))
      (node (ref "R5") (pin "C2") (pinfunction "W_C2") (pintype "passive"))
    )
    (net (code "61") (name "Net-(R6B-W)") (class "Default")
      (node (ref "R42") (pin "P$3") (pinfunction "P$3_P$3") (pintype "bidirectional"))
      (node (ref "R6") (pin "C2") (pinfunction "W_C2") (pintype "passive"))
    )
    (net (code "62") (name "Net-(R7B-W)") (class "Default")
      (node (ref "R42") (pin "P$5") (pinfunction "P$5_P$5") (pintype "bidirectional"))
      (node (ref "R7") (pin "C2") (pinfunction "W_C2") (pintype "passive"))
    )
    (net (code "63") (name "Net-(R8B-W)") (class "Default")
      (node (ref "R42") (pin "P$7") (pinfunction "P$7_P$7") (pintype "bidirectional"))
      (node (ref "R8") (pin "C2") (pinfunction "W_C2") (pintype "passive"))
    )
    (net (code "64") (name "Net-(R9B-W)") (class "Default")
      (node (ref "R43") (pin "P$1") (pinfunction "P$1_P$1") (pintype "bidirectional"))
      (node (ref "R9") (pin "C2") (pinfunction "W_C2") (pintype "passive"))
    )
    (net (code "65") (name "Net-(R10B-W)") (class "Default")
      (node (ref "R10") (pin "C2") (pinfunction "W_C2") (pintype "passive"))
      (node (ref "R43") (pin "P$3") (pinfunction "P$3_P$3") (pintype "bidirectional"))
    )
    (net (code "66") (name "Net-(R11B-W)") (class "Default")
      (node (ref "R11") (pin "C2") (pinfunction "W_C2") (pintype "passive"))
      (node (ref "R43") (pin "P$5") (pinfunction "P$5_P$5") (pintype "bidirectional"))
    )
    (net (code "67") (name "Net-(R12B-W)") (class "Default")
      (node (ref "R12") (pin "C2") (pinfunction "W_C2") (pintype "passive"))
      (node (ref "R43") (pin "P$7") (pinfunction "P$7_P$7") (pintype "bidirectional"))
    )
    (net (code "68") (name "Net-(R13B-W)") (class "Default")
      (node (ref "R13") (pin "C2") (pinfunction "W_C2") (pintype "passive"))
      (node (ref "R44") (pin "P$1") (pinfunction "P$1_P$1") (pintype "bidirectional"))
    )
    (net (code "69") (name "Net-(R14B-W)") (class "Default")
      (node (ref "R14") (pin "C2") (pinfunction "W_C2") (pintype "passive"))
      (node (ref "R44") (pin "P$3") (pinfunction "P$3_P$3") (pintype "bidirectional"))
    )
    (net (code "70") (name "Net-(R15B-W)") (class "Default")
      (node (ref "R15") (pin "C2") (pinfunction "W_C2") (pintype "passive"))
      (node (ref "R44") (pin "P$5") (pinfunction "P$5_P$5") (pintype "bidirectional"))
    )
    (net (code "71") (name "Net-(R16B-W)") (class "Default")
      (node (ref "R16") (pin "C2") (pinfunction "W_C2") (pintype "passive"))
      (node (ref "R44") (pin "P$7") (pinfunction "P$7_P$7") (pintype "bidirectional"))
    )
    (net (code "72") (name "Net-(SW1-P)") (class "Default")
      (node (ref "R21") (pin "2") (pinfunction "2_2") (pintype "passive"))
      (node (ref "SW1") (pin "C2") (pinfunction "P_C2") (pintype "passive"))
    )
    (net (code "73") (name "Net-(SW2-P)") (class "Default")
      (node (ref "R22") (pin "2") (pinfunction "2_2") (pintype "passive"))
      (node (ref "SW2") (pin "C2") (pinfunction "P_C2") (pintype "passive"))
    )
    (net (code "74") (name "Net-(SW3-P)") (class "Default")
      (node (ref "R23") (pin "2") (pinfunction "2_2") (pintype "passive"))
      (node (ref "SW3") (pin "C2") (pinfunction "P_C2") (pintype "passive"))
    )
    (net (code "75") (name "Net-(SW4-P)") (class "Default")
      (node (ref "R24") (pin "2") (pinfunction "2_2") (pintype "passive"))
      (node (ref "SW4") (pin "C2") (pinfunction "P_C2") (pintype "passive"))
    )
    (net (code "76") (name "Net-(SW5-P)") (class "Default")
      (node (ref "R25") (pin "2") (pinfunction "2_2") (pintype "passive"))
      (node (ref "SW5") (pin "C2") (pinfunction "P_C2") (pintype "passive"))
    )
    (net (code "77") (name "Net-(SW6-P)") (class "Default")
      (node (ref "R26") (pin "2") (pinfunction "2_2") (pintype "passive"))
      (node (ref "SW6") (pin "C2") (pinfunction "P_C2") (pintype "passive"))
    )
    (net (code "78") (name "Net-(SW7-P)") (class "Default")
      (node (ref "R27") (pin "2") (pinfunction "2_2") (pintype "passive"))
      (node (ref "SW7") (pin "C2") (pinfunction "P_C2") (pintype "passive"))
    )
    (net (code "79") (name "Net-(SW8-P)") (class "Default")
      (node (ref "R28") (pin "2") (pinfunction "2_2") (pintype "passive"))
      (node (ref "SW8") (pin "C2") (pinfunction "P_C2") (pintype "passive"))
    )
    (net (code "80") (name "Net-(SW9-P)") (class "Default")
      (node (ref "R29") (pin "2") (pinfunction "2_2") (pintype "passive"))
      (node (ref "SW9") (pin "C2") (pinfunction "P_C2") (pintype "passive"))
    )
    (net (code "81") (name "Net-(SW10-P)") (class "Default")
      (node (ref "R30") (pin "2") (pinfunction "2_2") (pintype "passive"))
      (node (ref "SW10") (pin "C2") (pinfunction "P_C2") (pintype "passive"))
    )
    (net (code "82") (name "Net-(SW11-P)") (class "Default")
      (node (ref "R31") (pin "2") (pinfunction "2_2") (pintype "passive"))
      (node (ref "SW11") (pin "C2") (pinfunction "P_C2") (pintype "passive"))
    )
    (net (code "83") (name "Net-(SW12-P)") (class "Default")
      (node (ref "R32") (pin "2") (pinfunction "2_2") (pintype "passive"))
      (node (ref "SW12") (pin "C2") (pinfunction "P_C2") (pintype "passive"))
    )
    (net (code "84") (name "Net-(SW13-P)") (class "Default")
      (node (ref "R33") (pin "2") (pinfunction "2_2") (pintype "passive"))
      (node (ref "SW13") (pin "C2") (pinfunction "P_C2") (pintype "passive"))
    )
    (net (code "85") (name "Net-(SW14-P)") (class "Default")
      (node (ref "R34") (pin "2") (pinfunction "2_2") (pintype "passive"))
      (node (ref "SW14") (pin "C2") (pinfunction "P_C2") (pintype "passive"))
    )
    (net (code "86") (name "Net-(SW15-P)") (class "Default")
      (node (ref "R35") (pin "2") (pinfunction "2_2") (pintype "passive"))
      (node (ref "SW15") (pin "C2") (pinfunction "P_C2") (pintype "passive"))
    )
    (net (code "87") (name "Net-(SW16-P)") (class "Default")
      (node (ref "R36") (pin "2") (pinfunction "2_2") (pintype "passive"))
      (node (ref "SW16") (pin "C2") (pinfunction "P_C2") (pintype "passive"))
    )
    (net (code "88") (name "unconnected-(SW1-S-PadC3)") (class "Default")
      (node (ref "SW1") (pin "C3") (pinfunction "S_C3") (pintype "passive"))
    )
    (net (code "89") (name "unconnected-(SW2-S-PadC3)") (class "Default")
      (node (ref "SW2") (pin "C3") (pinfunction "S_C3") (pintype "passive"))
    )
    (net (code "90") (name "unconnected-(SW3-S-PadC3)") (class "Default")
      (node (ref "SW3") (pin "C3") (pinfunction "S_C3") (pintype "passive"))
    )
    (net (code "91") (name "unconnected-(SW4-S-PadC3)") (class "Default")
      (node (ref "SW4") (pin "C3") (pinfunction "S_C3") (pintype "passive"))
    )
    (net (code "92") (name "unconnected-(SW5-S-PadC3)") (class "Default")
      (node (ref "SW5") (pin "C3") (pinfunction "S_C3") (pintype "passive"))
    )
    (net (code "93") (name "unconnected-(SW6-S-PadC3)") (class "Default")
      (node (ref "SW6") (pin "C3") (pinfunction "S_C3") (pintype "passive"))
    )
    (net (code "94") (name "unconnected-(SW7-S-PadC3)") (class "Default")
      (node (ref "SW7") (pin "C3") (pinfunction "S_C3") (pintype "passive"))
    )
    (net (code "95") (name "unconnected-(SW8-S-PadC3)") (class "Default")
      (node (ref "SW8") (pin "C3") (pinfunction "S_C3") (pintype "passive"))
    )
    (net (code "96") (name "unconnected-(SW9-S-PadC3)") (class "Default")
      (node (ref "SW9") (pin "C3") (pinfunction "S_C3") (pintype "passive"))
    )
    (net (code "97") (name "unconnected-(SW10-S-PadC3)") (class "Default")
      (node (ref "SW10") (pin "C3") (pinfunction "S_C3") (pintype "passive"))
    )
    (net (code "98") (name "unconnected-(SW11-S-PadC3)") (class "Default")
      (node (ref "SW11") (pin "C3") (pinfunction "S_C3") (pintype "passive"))
    )
    (net (code "99") (name "unconnected-(SW12-S-PadC3)") (class "Default")
      (node (ref "SW12") (pin "C3") (pinfunction "S_C3") (pintype "passive"))
    )
    (net (code "100") (name "unconnected-(SW13-S-PadC3)") (class "Default")
      (node (ref "SW13") (pin "C3") (pinfunction "S_C3") (pintype "passive"))
    )
    (net (code "101") (name "unconnected-(SW14-S-PadC3)") (class "Default")
      (node (ref "SW14") (pin "C3") (pinfunction "S_C3") (pintype "passive"))
    )
    (net (code "102") (name "unconnected-(SW15-S-PadC3)") (class "Default")
      (node (ref "SW15") (pin "C3") (pinfunction "S_C3") (pintype "passive"))
    )
    (net (code "103") (name "unconnected-(SW16-S-PadC3)") (class "Default")
      (node (ref "SW16") (pin "C3") (pinfunction "S_C3") (pintype "passive"))
    )
    (net (code "104") (name "unconnected-(SW17-O-PadC1)") (class "Default")
      (node (ref "SW17") (pin "C1") (pinfunction "O_C1") (pintype "passive"))
    )
  )
)
